# an205x_evb.net
KiCad netlist of a schematic drawn in Altium Designer
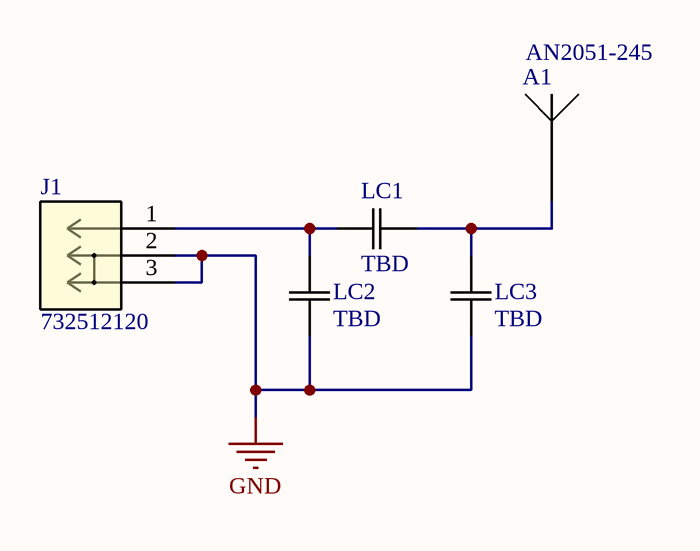
[diagram p0: an205x_evb.SchDoc]

(export (version "E")
  (design (tool "Eeschema 10.0.6"))
  (components
    (comp (ref "A1")
      (value "AN2051-245")
      (footprint "ANT_AN2051-245_RSN")
      (description "No Description Available")
      (fields (field (name "COPYRIGHT") "Copyright (C) 2022 Ultra Librarian. All rights reserved."))
      (libsource (lib "AN2051-245") (part "AN2051-245"))
    )
    (comp (ref "J1")
      (value "732512120")
      (footprint "CONN-732513152_MOL")
      (description "No Description Available")
      (fields (field (name "COPYRIGHT") "Copyright (C) 2022 Ultra Librarian. All rights reserved."))
      (libsource (lib "732512120") (part "732512120"))
    )
    (comp (ref "LC1")
      (value "TBD")
      (footprint "CAP_CC0402_YAG")
      (fields
        (field (name "MANUFACTURER_PART_NUMBER") "CC0402MRX5R6BB106")
        (field (name "COPYRIGHT") "Copyright (C) 2022 Ultra Librarian. All rights reserved.")
      )
      (libsource (lib "CC0402MRX5R6BB106") (part "CC0402MRX5R6BB106"))
    )
    (comp (ref "LC2")
      (value "TBD")
      (footprint "CAP_CC0402_YAG")
      (fields
        (field (name "MANUFACTURER_PART_NUMBER") "CC0402MRX5R6BB106")
        (field (name "COPYRIGHT") "Copyright (C) 2022 Ultra Librarian. All rights reserved.")
      )
      (libsource (lib "CC0402MRX5R6BB106") (part "CC0402MRX5R6BB106"))
    )
    (comp (ref "LC3")
      (value "TBD")
      (footprint "CAP_CC0402_YAG")
      (fields
        (field (name "MANUFACTURER_PART_NUMBER") "CC0402MRX5R6BB106")
        (field (name "COPYRIGHT") "Copyright (C) 2022 Ultra Librarian. All rights reserved.")
      )
      (libsource (lib "CC0402MRX5R6BB106") (part "CC0402MRX5R6BB106"))
    )
  )
  (nets
    (net (code "1") (name "GND") (class "Default")
      (node (ref "J1") (pin "2") (pinfunction "2_2") (pintype "passive"))
      (node (ref "J1") (pin "3") (pinfunction "3_3") (pintype "passive"))
      (node (ref "LC2") (pin "1") (pinfunction "1_1") (pintype "passive"))
      (node (ref "LC3") (pin "1") (pinfunction "1_1") (pintype "passive"))
    )
    (net (code "2") (name "Net-(A1-Pad1)") (class "Default")
      (node (ref "A1") (pin "1") (pinfunction "1_1") (pintype "passive"))
      (node (ref "LC1") (pin "2") (pinfunction "2_2") (pintype "passive"))
      (node (ref "LC3") (pin "2") (pinfunction "2_2") (pintype "passive"))
    )
    (net (code "3") (name "Net-(J1-Pad1)") (class "Default")
      (node (ref "J1") (pin "1") (pinfunction "1_1") (pintype "passive"))
      (node (ref "LC1") (pin "1") (pinfunction "1_1") (pintype "passive"))
      (node (ref "LC2") (pin "2") (pinfunction "2_2") (pintype "passive"))
    )
  )
)
